# power_switcher.net
KiCad netlist of a schematic drawn in EAGLE
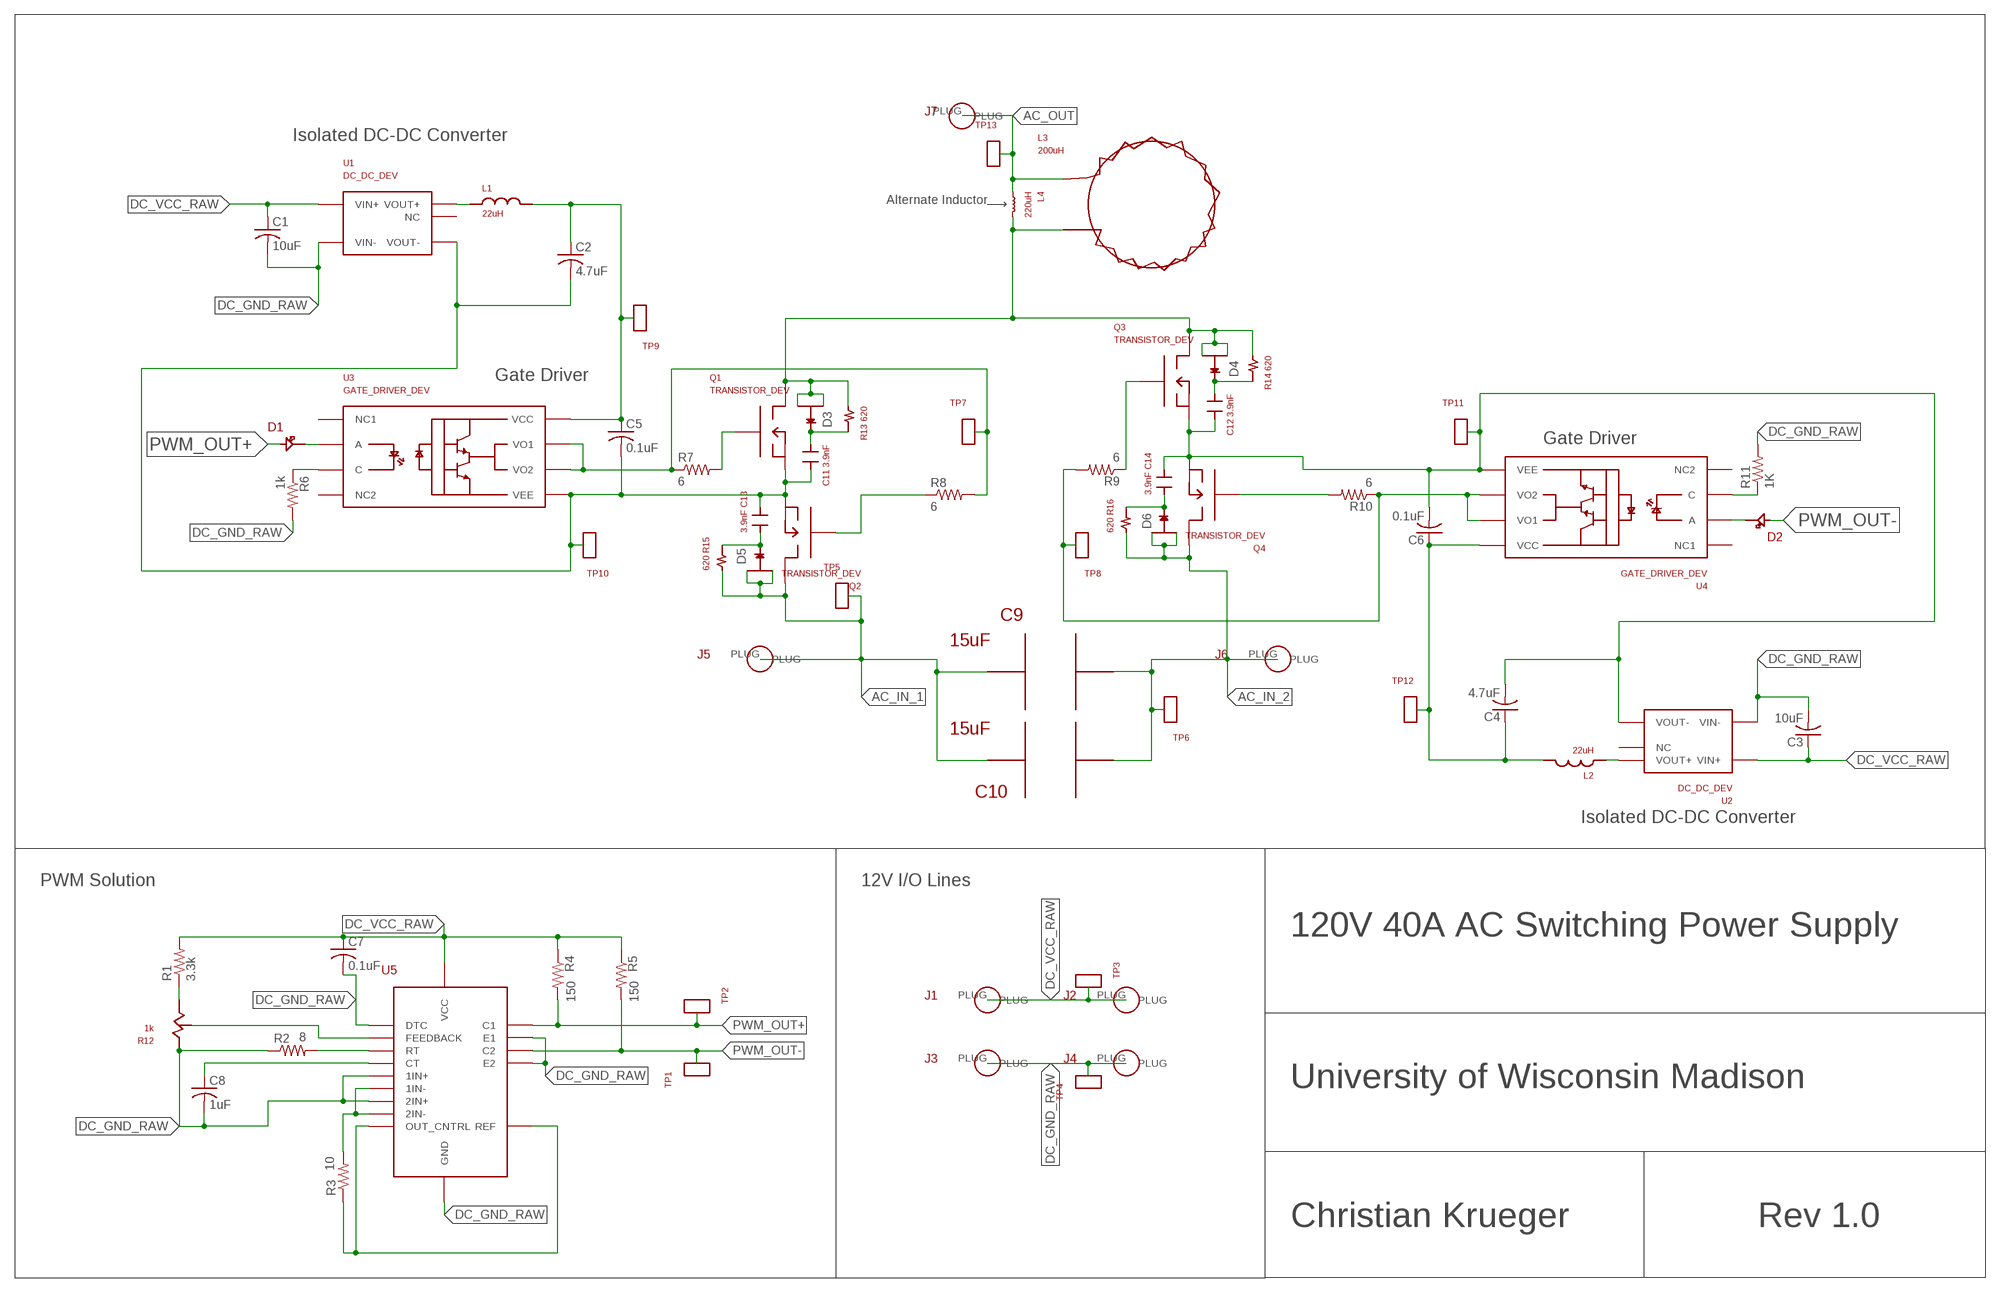
[diagram p0: schematic, sheet 1]

(export (version "E")
  (design (tool "Eeschema 10.0.6"))
  (components
    (comp (ref "C1")
      (value "10uF")
      (footprint "eagle-import:C0805")
      (libsource (lib "eagle-import") (part "C-USC0805"))
    )
    (comp (ref "C2")
      (value "4.7uF")
      (footprint "eagle-import:C0805")
      (libsource (lib "eagle-import") (part "C-USC0805"))
    )
    (comp (ref "C3")
      (value "10uF")
      (footprint "eagle-import:C0805")
      (libsource (lib "eagle-import") (part "C-USC0805"))
    )
    (comp (ref "C4")
      (value "4.7uF")
      (footprint "eagle-import:C0805")
      (libsource (lib "eagle-import") (part "C-USC0805"))
    )
    (comp (ref "C5")
      (value "0.1uF")
      (footprint "eagle-import:C0805")
      (libsource (lib "eagle-import") (part "C-USC0805"))
    )
    (comp (ref "C6")
      (value "0.1uF")
      (footprint "eagle-import:C0805")
      (libsource (lib "eagle-import") (part "C-USC0805"))
    )
    (comp (ref "C7")
      (value "0.1uF")
      (footprint "eagle-import:C0805")
      (libsource (lib "eagle-import") (part "C-USC0805"))
    )
    (comp (ref "C8")
      (value "1uF")
      (footprint "eagle-import:C0805")
      (libsource (lib "eagle-import") (part "C-USC0805"))
    )
    (comp (ref "C9")
      (value "15uF")
      (footprint "eagle-import:BIG_ASS_CAP_PKG")
      (libsource (lib "eagle-import") (part "BIG_AS_CAP_DEV"))
    )
    (comp (ref "C10")
      (value "15uF")
      (footprint "eagle-import:BIG_ASS_CAP_PKG")
      (libsource (lib "eagle-import") (part "BIG_AS_CAP_DEV"))
    )
    (comp (ref "C11")
      (value "3.9nF")
      (footprint "eagle-import:0805_GEN_PKG")
      (libsource (lib "eagle-import") (part "GEN_CAP"))
    )
    (comp (ref "C12")
      (value "3.9nF")
      (footprint "eagle-import:0805_GEN_PKG")
      (libsource (lib "eagle-import") (part "GEN_CAP"))
    )
    (comp (ref "C13")
      (value "3.9nF")
      (footprint "eagle-import:0805_GEN_PKG")
      (libsource (lib "eagle-import") (part "GEN_CAP"))
    )
    (comp (ref "C14")
      (value "3.9nF")
      (footprint "eagle-import:0805_GEN_PKG")
      (libsource (lib "eagle-import") (part "GEN_CAP"))
    )
    (comp (ref "D1")
      (value "LED_DEV")
      (footprint "eagle-import:0805_PKG")
      (libsource (lib "eagle-import") (part "LED_DEV"))
    )
    (comp (ref "D2")
      (value "LED_DEV")
      (footprint "eagle-import:0805_PKG")
      (libsource (lib "eagle-import") (part "LED_DEV"))
    )
    (comp (ref "D3")
      (value "D2PAK_DIODE_DEV")
      (footprint "eagle-import:D2PAK_PKG")
      (libsource (lib "eagle-import") (part "D2PAK_DIODE_DEV"))
    )
    (comp (ref "D4")
      (value "D2PAK_DIODE_DEV")
      (footprint "eagle-import:D2PAK_PKG")
      (libsource (lib "eagle-import") (part "D2PAK_DIODE_DEV"))
    )
    (comp (ref "D5")
      (value "D2PAK_DIODE_DEV")
      (footprint "eagle-import:D2PAK_PKG")
      (libsource (lib "eagle-import") (part "D2PAK_DIODE_DEV"))
    )
    (comp (ref "D6")
      (value "D2PAK_DIODE_DEV")
      (footprint "eagle-import:D2PAK_PKG")
      (libsource (lib "eagle-import") (part "D2PAK_DIODE_DEV"))
    )
    (comp (ref "J1")
      (value "BANNANA_DEV")
      (footprint "eagle-import:BANNANA_PKG")
      (libsource (lib "eagle-import") (part "BANNANA_DEV"))
    )
    (comp (ref "J2")
      (value "BANNANA_DEV")
      (footprint "eagle-import:BANNANA_PKG")
      (libsource (lib "eagle-import") (part "BANNANA_DEV"))
    )
    (comp (ref "J3")
      (value "BANNANA_DEV")
      (footprint "eagle-import:BANNANA_PKG")
      (libsource (lib "eagle-import") (part "BANNANA_DEV"))
    )
    (comp (ref "J4")
      (value "BANNANA_DEV")
      (footprint "eagle-import:BANNANA_PKG")
      (libsource (lib "eagle-import") (part "BANNANA_DEV"))
    )
    (comp (ref "J5")
      (value "BANNANA_DEV")
      (footprint "eagle-import:BANNANA_PKG")
      (libsource (lib "eagle-import") (part "BANNANA_DEV"))
    )
    (comp (ref "J6")
      (value "BANNANA_DEV")
      (footprint "eagle-import:BANNANA_PKG")
      (libsource (lib "eagle-import") (part "BANNANA_DEV"))
    )
    (comp (ref "J7")
      (value "BANNANA_DEV")
      (footprint "eagle-import:BANNANA_PKG")
      (libsource (lib "eagle-import") (part "BANNANA_DEV"))
    )
    (comp (ref "L1")
      (value "22uH")
      (footprint "eagle-import:0805RES_DEV")
      (libsource (lib "eagle-import") (part "0805IND_DEV"))
    )
    (comp (ref "L2")
      (value "22uH")
      (footprint "eagle-import:0805RES_DEV")
      (libsource (lib "eagle-import") (part "0805IND_DEV"))
    )
    (comp (ref "L3")
      (value "200uH")
      (footprint "eagle-import:BIG_ASS_INDUCTOR_PKG")
      (libsource (lib "eagle-import") (part "BIG_ASS_INDUCTOR"))
    )
    (comp (ref "L4")
      (value "220uH")
      (footprint "eagle-import:ALT_IND_PKG")
      (libsource (lib "eagle-import") (part "ALT_IND_DEV"))
    )
    (comp (ref "Q1")
      (value "TRANSISTOR_DEV")
      (footprint "eagle-import:TRANSISTOR_PKG")
      (libsource (lib "eagle-import") (part "TRANSISTOR_DEV"))
    )
    (comp (ref "Q2")
      (value "TRANSISTOR_DEV")
      (footprint "eagle-import:TRANSISTOR_PKG")
      (libsource (lib "eagle-import") (part "TRANSISTOR_DEV"))
    )
    (comp (ref "Q3")
      (value "TRANSISTOR_DEV")
      (footprint "eagle-import:TRANSISTOR_PKG")
      (libsource (lib "eagle-import") (part "TRANSISTOR_DEV"))
    )
    (comp (ref "Q4")
      (value "TRANSISTOR_DEV")
      (footprint "eagle-import:TRANSISTOR_PKG")
      (libsource (lib "eagle-import") (part "TRANSISTOR_DEV"))
    )
    (comp (ref "R1")
      (value "3.3k")
      (footprint "eagle-import:M0805")
      (libsource (lib "eagle-import") (part "R-US_M0805"))
    )
    (comp (ref "R2")
      (value "8")
      (footprint "eagle-import:M0805")
      (libsource (lib "eagle-import") (part "R-US_M0805"))
    )
    (comp (ref "R3")
      (value "10")
      (footprint "eagle-import:M0805")
      (libsource (lib "eagle-import") (part "R-US_M0805"))
    )
    (comp (ref "R4")
      (value "150")
      (footprint "eagle-import:M0805")
      (libsource (lib "eagle-import") (part "R-US_M0805"))
    )
    (comp (ref "R5")
      (value "150")
      (footprint "eagle-import:M0805")
      (libsource (lib "eagle-import") (part "R-US_M0805"))
    )
    (comp (ref "R6")
      (value "1k")
      (footprint "eagle-import:M0805")
      (libsource (lib "eagle-import") (part "R-US_M0805"))
    )
    (comp (ref "R7")
      (value "6")
      (footprint "eagle-import:M0805")
      (libsource (lib "eagle-import") (part "R-US_M0805"))
    )
    (comp (ref "R8")
      (value "6")
      (footprint "eagle-import:M0805")
      (libsource (lib "eagle-import") (part "R-US_M0805"))
    )
    (comp (ref "R9")
      (value "6")
      (footprint "eagle-import:M0805")
      (libsource (lib "eagle-import") (part "R-US_M0805"))
    )
    (comp (ref "R10")
      (value "6")
      (footprint "eagle-import:M0805")
      (libsource (lib "eagle-import") (part "R-US_M0805"))
    )
    (comp (ref "R11")
      (value "1K")
      (footprint "eagle-import:M0805")
      (libsource (lib "eagle-import") (part "R-US_M0805"))
    )
    (comp (ref "R12")
      (value "1k")
      (footprint "eagle-import:POT_SLIDER_PKG")
      (libsource (lib "eagle-import") (part "SLIDE_POT_DEV"))
    )
    (comp (ref "R13")
      (value "620")
      (footprint "eagle-import:2512_PKG")
      (libsource (lib "eagle-import") (part "2512_RES"))
    )
    (comp (ref "R14")
      (value "620")
      (footprint "eagle-import:2512_PKG")
      (libsource (lib "eagle-import") (part "2512_RES"))
    )
    (comp (ref "R15")
      (value "620")
      (footprint "eagle-import:2512_PKG")
      (libsource (lib "eagle-import") (part "2512_RES"))
    )
    (comp (ref "R16")
      (value "620")
      (footprint "eagle-import:2512_PKG")
      (libsource (lib "eagle-import") (part "2512_RES"))
    )
    (comp (ref "TP1")
      (value "TEST_POINT")
      (footprint "eagle-import:0805_GEN_PKG")
      (libsource (lib "eagle-import") (part "TEST_POINT"))
    )
    (comp (ref "TP2")
      (value "TEST_POINT")
      (footprint "eagle-import:0805_GEN_PKG")
      (libsource (lib "eagle-import") (part "TEST_POINT"))
    )
    (comp (ref "TP3")
      (value "TEST_POINT")
      (footprint "eagle-import:0805_GEN_PKG")
      (libsource (lib "eagle-import") (part "TEST_POINT"))
    )
    (comp (ref "TP4")
      (value "TEST_POINT")
      (footprint "eagle-import:0805_GEN_PKG")
      (libsource (lib "eagle-import") (part "TEST_POINT"))
    )
    (comp (ref "TP5")
      (value "TEST_POINT")
      (footprint "eagle-import:0805_GEN_PKG")
      (libsource (lib "eagle-import") (part "TEST_POINT"))
    )
    (comp (ref "TP6")
      (value "TEST_POINT")
      (footprint "eagle-import:0805_GEN_PKG")
      (libsource (lib "eagle-import") (part "TEST_POINT"))
    )
    (comp (ref "TP7")
      (value "TEST_POINT")
      (footprint "eagle-import:0805_GEN_PKG")
      (libsource (lib "eagle-import") (part "TEST_POINT"))
    )
    (comp (ref "TP8")
      (value "TEST_POINT")
      (footprint "eagle-import:0805_GEN_PKG")
      (libsource (lib "eagle-import") (part "TEST_POINT"))
    )
    (comp (ref "TP9")
      (value "TEST_POINT")
      (footprint "eagle-import:0805_GEN_PKG")
      (libsource (lib "eagle-import") (part "TEST_POINT"))
    )
    (comp (ref "TP10")
      (value "TEST_POINT")
      (footprint "eagle-import:0805_GEN_PKG")
      (libsource (lib "eagle-import") (part "TEST_POINT"))
    )
    (comp (ref "TP11")
      (value "TEST_POINT")
      (footprint "eagle-import:0805_GEN_PKG")
      (libsource (lib "eagle-import") (part "TEST_POINT"))
    )
    (comp (ref "TP12")
      (value "TEST_POINT")
      (footprint "eagle-import:0805_GEN_PKG")
      (libsource (lib "eagle-import") (part "TEST_POINT"))
    )
    (comp (ref "TP13")
      (value "TEST_POINT")
      (footprint "eagle-import:0805_GEN_PKG")
      (libsource (lib "eagle-import") (part "TEST_POINT"))
    )
    (comp (ref "U1")
      (value "DC_DC_DEV")
      (footprint "eagle-import:DC_DC_PKG")
      (libsource (lib "eagle-import") (part "DC_DC_DEV"))
    )
    (comp (ref "U2")
      (value "DC_DC_DEV")
      (footprint "eagle-import:DC_DC_PKG")
      (libsource (lib "eagle-import") (part "DC_DC_DEV"))
    )
    (comp (ref "U3")
      (value "GATE_DRIVER_DEV")
      (footprint "eagle-import:GATE_DRIVER_PKG")
      (libsource (lib "eagle-import") (part "GATE_DRIVER_DEV"))
    )
    (comp (ref "U4")
      (value "GATE_DRIVER_DEV")
      (footprint "eagle-import:GATE_DRIVER_PKG")
      (libsource (lib "eagle-import") (part "GATE_DRIVER_DEV"))
    )
    (comp (ref "U5")
      (value "PWM_DRIVER_DEV")
      (footprint "eagle-import:PWM_DRIVER_PKG")
      (libsource (lib "eagle-import") (part "PWM_DRIVER_DEV"))
    )
  )
  (nets
    (net (code "1") (name "AC_IN_1") (class "Default")
      (node (ref "C10") (pin "P$1") (pinfunction "P$1_P$1") (pintype "bidirectional"))
      (node (ref "C9") (pin "P$1") (pinfunction "P$1_P$1") (pintype "bidirectional"))
      (node (ref "D5") (pin "IN1") (pinfunction "IN1_IN1") (pintype "bidirectional"))
      (node (ref "D5") (pin "IN2") (pinfunction "IN2_IN2") (pintype "bidirectional"))
      (node (ref "J5") (pin "PLUG") (pinfunction "PLUG_PLUG") (pintype "bidirectional"))
      (node (ref "Q2") (pin "D") (pinfunction "DRAIN_D") (pintype "bidirectional"))
      (node (ref "R15") (pin "P$1") (pinfunction "P$1_P$1") (pintype "bidirectional"))
      (node (ref "TP5") (pin "P$1") (pinfunction "P$1_P$1") (pintype "bidirectional"))
    )
    (net (code "2") (name "AC_IN_2") (class "Default")
      (node (ref "C10") (pin "P$2") (pinfunction "P$2_P$2") (pintype "bidirectional"))
      (node (ref "C9") (pin "P$2") (pinfunction "P$2_P$2") (pintype "bidirectional"))
      (node (ref "D6") (pin "IN1") (pinfunction "IN1_IN1") (pintype "bidirectional"))
      (node (ref "D6") (pin "IN2") (pinfunction "IN2_IN2") (pintype "bidirectional"))
      (node (ref "J6") (pin "PLUG") (pinfunction "PLUG_PLUG") (pintype "bidirectional"))
      (node (ref "Q4") (pin "D") (pinfunction "DRAIN_D") (pintype "bidirectional"))
      (node (ref "R16") (pin "P$1") (pinfunction "P$1_P$1") (pintype "bidirectional"))
      (node (ref "TP6") (pin "P$1") (pinfunction "P$1_P$1") (pintype "bidirectional"))
    )
    (net (code "3") (name "AC_OUT") (class "Default")
      (node (ref "J7") (pin "PLUG") (pinfunction "PLUG_PLUG") (pintype "bidirectional"))
      (node (ref "L3") (pin "P$1") (pinfunction "P$1_P$1") (pintype "bidirectional"))
      (node (ref "L4") (pin "P$1") (pinfunction "P$1_P$1") (pintype "bidirectional"))
      (node (ref "TP13") (pin "P$1") (pinfunction "P$1_P$1") (pintype "bidirectional"))
    )
    (net (code "4") (name "DC_GND_RAW") (class "Default")
      (node (ref "C1") (pin "2") (pinfunction "2_2") (pintype "passive"))
      (node (ref "C3") (pin "2") (pinfunction "2_2") (pintype "passive"))
      (node (ref "C7") (pin "2") (pinfunction "2_2") (pintype "passive"))
      (node (ref "C8") (pin "2") (pinfunction "2_2") (pintype "passive"))
      (node (ref "J3") (pin "PLUG") (pinfunction "PLUG_PLUG") (pintype "bidirectional"))
      (node (ref "J4") (pin "PLUG") (pinfunction "PLUG_PLUG") (pintype "bidirectional"))
      (node (ref "R11") (pin "2") (pinfunction "2_2") (pintype "passive"))
      (node (ref "R12") (pin "3") (pinfunction "1_3") (pintype "bidirectional"))
      (node (ref "R2") (pin "1") (pinfunction "1_1") (pintype "passive"))
      (node (ref "R6") (pin "2") (pinfunction "2_2") (pintype "passive"))
      (node (ref "TP4") (pin "P$1") (pinfunction "P$1_P$1") (pintype "bidirectional"))
      (node (ref "U1") (pin "-VIN") (pinfunction "VIN-_-VIN") (pintype "bidirectional"))
      (node (ref "U2") (pin "-VIN") (pinfunction "VIN-_-VIN") (pintype "bidirectional"))
      (node (ref "U5") (pin "P$1") (pinfunction "1IN+_P$1") (pintype "bidirectional"))
      (node (ref "U5") (pin "P$10") (pinfunction "E2_P$10") (pintype "bidirectional"))
      (node (ref "U5") (pin "P$16") (pinfunction "2IN+_P$16") (pintype "bidirectional"))
      (node (ref "U5") (pin "P$4") (pinfunction "DTC_P$4") (pintype "bidirectional"))
      (node (ref "U5") (pin "P$7") (pinfunction "GND_P$7") (pintype "bidirectional"))
      (node (ref "U5") (pin "P$9") (pinfunction "E1_P$9") (pintype "bidirectional"))
    )
    (net (code "5") (name "DC_VCC_RAW") (class "Default")
      (node (ref "C1") (pin "1") (pinfunction "1_1") (pintype "passive"))
      (node (ref "C3") (pin "1") (pinfunction "1_1") (pintype "passive"))
      (node (ref "C7") (pin "1") (pinfunction "1_1") (pintype "passive"))
      (node (ref "J1") (pin "PLUG") (pinfunction "PLUG_PLUG") (pintype "bidirectional"))
      (node (ref "J2") (pin "PLUG") (pinfunction "PLUG_PLUG") (pintype "bidirectional"))
      (node (ref "R1") (pin "2") (pinfunction "2_2") (pintype "passive"))
      (node (ref "R4") (pin "1") (pinfunction "1_1") (pintype "passive"))
      (node (ref "R5") (pin "1") (pinfunction "1_1") (pintype "passive"))
      (node (ref "TP3") (pin "P$1") (pinfunction "P$1_P$1") (pintype "bidirectional"))
      (node (ref "U1") (pin "+VIN") (pinfunction "VIN+_+VIN") (pintype "bidirectional"))
      (node (ref "U2") (pin "+VIN") (pinfunction "VIN+_+VIN") (pintype "bidirectional"))
      (node (ref "U5") (pin "P$12") (pinfunction "VCC_P$12") (pintype "bidirectional"))
    )
    (net (code "6") (name "Net-(C11-PadP$1)") (class "Default")
      (node (ref "C11") (pin "P$1") (pinfunction "P$1_P$1") (pintype "bidirectional"))
      (node (ref "D3") (pin "OUT") (pinfunction "OUT_OUT") (pintype "bidirectional"))
      (node (ref "R13") (pin "P$2") (pinfunction "P$2_P$2") (pintype "bidirectional"))
    )
    (net (code "7") (name "Net-(C12-PadP$1)") (class "Default")
      (node (ref "C12") (pin "P$1") (pinfunction "P$1_P$1") (pintype "bidirectional"))
      (node (ref "D4") (pin "OUT") (pinfunction "OUT_OUT") (pintype "bidirectional"))
      (node (ref "R14") (pin "P$2") (pinfunction "P$2_P$2") (pintype "bidirectional"))
    )
    (net (code "8") (name "Net-(C13-PadP$1)") (class "Default")
      (node (ref "C13") (pin "P$1") (pinfunction "P$1_P$1") (pintype "bidirectional"))
      (node (ref "D5") (pin "OUT") (pinfunction "OUT_OUT") (pintype "bidirectional"))
      (node (ref "R15") (pin "P$2") (pinfunction "P$2_P$2") (pintype "bidirectional"))
    )
    (net (code "9") (name "Net-(C14-PadP$1)") (class "Default")
      (node (ref "C14") (pin "P$1") (pinfunction "P$1_P$1") (pintype "bidirectional"))
      (node (ref "D6") (pin "OUT") (pinfunction "OUT_OUT") (pintype "bidirectional"))
      (node (ref "R16") (pin "P$2") (pinfunction "P$2_P$2") (pintype "bidirectional"))
    )
    (net (code "10") (name "Net-(D1-PadP$2)") (class "Default")
      (node (ref "D1") (pin "P$2") (pinfunction "P$2_P$2") (pintype "bidirectional"))
      (node (ref "U3") (pin "A") (pinfunction "A_A") (pintype "bidirectional"))
    )
    (net (code "11") (name "Net-(D2-PadP$2)") (class "Default")
      (node (ref "D2") (pin "P$2") (pinfunction "P$2_P$2") (pintype "bidirectional"))
      (node (ref "U4") (pin "A") (pinfunction "A_A") (pintype "bidirectional"))
    )
    (net (code "12") (name "Net-(L1-P$1)") (class "Default")
      (node (ref "L1") (pin "L") (pinfunction "P$1_L") (pintype "bidirectional"))
      (node (ref "U1") (pin "+VOUT") (pinfunction "VOUT+_+VOUT") (pintype "bidirectional"))
    )
    (net (code "13") (name "Net-(L1-P$2)") (class "Default")
      (node (ref "C2") (pin "1") (pinfunction "1_1") (pintype "passive"))
      (node (ref "C5") (pin "1") (pinfunction "1_1") (pintype "passive"))
      (node (ref "L1") (pin "R") (pinfunction "P$2_R") (pintype "bidirectional"))
      (node (ref "TP9") (pin "P$1") (pinfunction "P$1_P$1") (pintype "bidirectional"))
      (node (ref "U3") (pin "VCC") (pinfunction "VCC_VCC") (pintype "bidirectional"))
    )
    (net (code "14") (name "Net-(L2-P$1)") (class "Default")
      (node (ref "L2") (pin "L") (pinfunction "P$1_L") (pintype "bidirectional"))
      (node (ref "U2") (pin "+VOUT") (pinfunction "VOUT+_+VOUT") (pintype "bidirectional"))
    )
    (net (code "15") (name "Net-(L2-P$2)") (class "Default")
      (node (ref "C4") (pin "1") (pinfunction "1_1") (pintype "passive"))
      (node (ref "C6") (pin "1") (pinfunction "1_1") (pintype "passive"))
      (node (ref "L2") (pin "R") (pinfunction "P$2_R") (pintype "bidirectional"))
      (node (ref "TP12") (pin "P$1") (pinfunction "P$1_P$1") (pintype "bidirectional"))
      (node (ref "U4") (pin "VCC") (pinfunction "VCC_VCC") (pintype "bidirectional"))
    )
    (net (code "16") (name "Net-(Q1-DRAIN)") (class "Default")
      (node (ref "D3") (pin "IN1") (pinfunction "IN1_IN1") (pintype "bidirectional"))
      (node (ref "D3") (pin "IN2") (pinfunction "IN2_IN2") (pintype "bidirectional"))
      (node (ref "D4") (pin "IN1") (pinfunction "IN1_IN1") (pintype "bidirectional"))
      (node (ref "D4") (pin "IN2") (pinfunction "IN2_IN2") (pintype "bidirectional"))
      (node (ref "L3") (pin "P$2") (pinfunction "P$2_P$2") (pintype "bidirectional"))
      (node (ref "L4") (pin "P$2") (pinfunction "P$2_P$2") (pintype "bidirectional"))
      (node (ref "Q1") (pin "D") (pinfunction "DRAIN_D") (pintype "bidirectional"))
      (node (ref "Q3") (pin "D") (pinfunction "DRAIN_D") (pintype "bidirectional"))
      (node (ref "R13") (pin "P$1") (pinfunction "P$1_P$1") (pintype "bidirectional"))
      (node (ref "R14") (pin "P$1") (pinfunction "P$1_P$1") (pintype "bidirectional"))
    )
    (net (code "17") (name "Net-(Q1-GATE)") (class "Default")
      (node (ref "Q1") (pin "G") (pinfunction "GATE_G") (pintype "bidirectional"))
      (node (ref "R7") (pin "2") (pinfunction "2_2") (pintype "passive"))
    )
    (net (code "18") (name "Net-(Q1-SOURCE)") (class "Default")
      (node (ref "C11") (pin "P$2") (pinfunction "P$2_P$2") (pintype "bidirectional"))
      (node (ref "C13") (pin "P$2") (pinfunction "P$2_P$2") (pintype "bidirectional"))
      (node (ref "C2") (pin "2") (pinfunction "2_2") (pintype "passive"))
      (node (ref "C5") (pin "2") (pinfunction "2_2") (pintype "passive"))
      (node (ref "Q1") (pin "S") (pinfunction "SOURCE_S") (pintype "bidirectional"))
      (node (ref "Q2") (pin "S") (pinfunction "SOURCE_S") (pintype "bidirectional"))
      (node (ref "TP10") (pin "P$1") (pinfunction "P$1_P$1") (pintype "bidirectional"))
      (node (ref "U1") (pin "-VOUT") (pinfunction "VOUT-_-VOUT") (pintype "bidirectional"))
      (node (ref "U3") (pin "VEE") (pinfunction "VEE_VEE") (pintype "bidirectional"))
    )
    (net (code "19") (name "Net-(Q2-GATE)") (class "Default")
      (node (ref "Q2") (pin "G") (pinfunction "GATE_G") (pintype "bidirectional"))
      (node (ref "R8") (pin "1") (pinfunction "1_1") (pintype "passive"))
    )
    (net (code "20") (name "Net-(Q3-GATE)") (class "Default")
      (node (ref "Q3") (pin "G") (pinfunction "GATE_G") (pintype "bidirectional"))
      (node (ref "R9") (pin "1") (pinfunction "1_1") (pintype "passive"))
    )
    (net (code "21") (name "Net-(Q3-SOURCE)") (class "Default")
      (node (ref "C12") (pin "P$2") (pinfunction "P$2_P$2") (pintype "bidirectional"))
      (node (ref "C14") (pin "P$2") (pinfunction "P$2_P$2") (pintype "bidirectional"))
      (node (ref "C4") (pin "2") (pinfunction "2_2") (pintype "passive"))
      (node (ref "C6") (pin "2") (pinfunction "2_2") (pintype "passive"))
      (node (ref "Q3") (pin "S") (pinfunction "SOURCE_S") (pintype "bidirectional"))
      (node (ref "Q4") (pin "S") (pinfunction "SOURCE_S") (pintype "bidirectional"))
      (node (ref "TP11") (pin "P$1") (pinfunction "P$1_P$1") (pintype "bidirectional"))
      (node (ref "U2") (pin "-VOUT") (pinfunction "VOUT-_-VOUT") (pintype "bidirectional"))
      (node (ref "U4") (pin "VEE") (pinfunction "VEE_VEE") (pintype "bidirectional"))
    )
    (net (code "22") (name "Net-(Q4-GATE)") (class "Default")
      (node (ref "Q4") (pin "G") (pinfunction "GATE_G") (pintype "bidirectional"))
      (node (ref "R10") (pin "2") (pinfunction "2_2") (pintype "passive"))
    )
    (net (code "23") (name "Net-(R6-Pad1)") (class "Default")
      (node (ref "R6") (pin "1") (pinfunction "1_1") (pintype "passive"))
      (node (ref "U3") (pin "C") (pinfunction "C_C") (pintype "bidirectional"))
    )
    (net (code "24") (name "Net-(R7-Pad1)") (class "Default")
      (node (ref "R7") (pin "1") (pinfunction "1_1") (pintype "passive"))
      (node (ref "R8") (pin "2") (pinfunction "2_2") (pintype "passive"))
      (node (ref "TP7") (pin "P$1") (pinfunction "P$1_P$1") (pintype "bidirectional"))
      (node (ref "U3") (pin "VO1") (pinfunction "VO1_VO1") (pintype "bidirectional"))
      (node (ref "U3") (pin "VO2") (pinfunction "VO2_VO2") (pintype "bidirectional"))
    )
    (net (code "25") (name "Net-(R10-Pad1)") (class "Default")
      (node (ref "R10") (pin "1") (pinfunction "1_1") (pintype "passive"))
      (node (ref "R9") (pin "2") (pinfunction "2_2") (pintype "passive"))
      (node (ref "TP8") (pin "P$1") (pinfunction "P$1_P$1") (pintype "bidirectional"))
      (node (ref "U4") (pin "VO1") (pinfunction "VO1_VO1") (pintype "bidirectional"))
      (node (ref "U4") (pin "VO2") (pinfunction "VO2_VO2") (pintype "bidirectional"))
    )
    (net (code "26") (name "Net-(R11-Pad1)") (class "Default")
      (node (ref "R11") (pin "1") (pinfunction "1_1") (pintype "passive"))
      (node (ref "U4") (pin "C") (pinfunction "C_C") (pintype "bidirectional"))
    )
    (net (code "27") (name "Net-(R12-2)") (class "Default")
      (node (ref "R1") (pin "1") (pinfunction "1_1") (pintype "passive"))
      (node (ref "R12") (pin "1") (pinfunction "2_1") (pintype "bidirectional"))
    )
    (net (code "28") (name "Net-(R12-VAR)") (class "Default")
      (node (ref "R12") (pin "2") (pinfunction "VAR_2") (pintype "bidirectional"))
      (node (ref "U5") (pin "P$3") (pinfunction "FEEDBACK_P$3") (pintype "bidirectional"))
    )
    (net (code "29") (name "Net-(U5-1IN-)") (class "Default")
      (node (ref "R3") (pin "2") (pinfunction "2_2") (pintype "passive"))
      (node (ref "U5") (pin "P$15") (pinfunction "2IN-_P$15") (pintype "bidirectional"))
      (node (ref "U5") (pin "P$2") (pinfunction "1IN-_P$2") (pintype "bidirectional"))
    )
    (net (code "30") (name "Net-(U5-CT)") (class "Default")
      (node (ref "C8") (pin "1") (pinfunction "1_1") (pintype "passive"))
      (node (ref "U5") (pin "P$5") (pinfunction "CT_P$5") (pintype "bidirectional"))
    )
    (net (code "31") (name "Net-(U5-OUT_CNTRL)") (class "Default")
      (node (ref "R3") (pin "1") (pinfunction "1_1") (pintype "passive"))
      (node (ref "U5") (pin "P$13") (pinfunction "OUT_CNTRL_P$13") (pintype "bidirectional"))
      (node (ref "U5") (pin "P$14") (pinfunction "REF_P$14") (pintype "bidirectional"))
    )
    (net (code "32") (name "Net-(U5-RT)") (class "Default")
      (node (ref "R2") (pin "2") (pinfunction "2_2") (pintype "passive"))
      (node (ref "U5") (pin "P$6") (pinfunction "RT_P$6") (pintype "bidirectional"))
    )
    (net (code "33") (name "PWM_OUT+") (class "Default")
      (node (ref "D1") (pin "P$1") (pinfunction "P$1_P$1") (pintype "bidirectional"))
      (node (ref "R4") (pin "2") (pinfunction "2_2") (pintype "passive"))
      (node (ref "TP2") (pin "P$1") (pinfunction "P$1_P$1") (pintype "bidirectional"))
      (node (ref "U5") (pin "P$8") (pinfunction "C1_P$8") (pintype "bidirectional"))
    )
    (net (code "34") (name "PWM_OUT-") (class "Default")
      (node (ref "D2") (pin "P$1") (pinfunction "P$1_P$1") (pintype "bidirectional"))
      (node (ref "R5") (pin "2") (pinfunction "2_2") (pintype "passive"))
      (node (ref "TP1") (pin "P$1") (pinfunction "P$1_P$1") (pintype "bidirectional"))
      (node (ref "U5") (pin "P$11") (pinfunction "C2_P$11") (pintype "bidirectional"))
    )
    (net (code "35") (name "unconnected-(U1-PadNC)") (class "Default")
      (node (ref "U1") (pin "NC") (pinfunction "NC_NC") (pintype "bidirectional"))
    )
    (net (code "36") (name "unconnected-(U2-PadNC)") (class "Default")
      (node (ref "U2") (pin "NC") (pinfunction "NC_NC") (pintype "bidirectional"))
    )
    (net (code "37") (name "unconnected-(U3-PadNC1)") (class "Default")
      (node (ref "U3") (pin "NC1") (pinfunction "NC1_NC1") (pintype "bidirectional"))
    )
    (net (code "38") (name "unconnected-(U3-PadNC2)") (class "Default")
      (node (ref "U3") (pin "NC2") (pinfunction "NC2_NC2") (pintype "bidirectional"))
    )
    (net (code "39") (name "unconnected-(U4-PadNC1)") (class "Default")
      (node (ref "U4") (pin "NC1") (pinfunction "NC1_NC1") (pintype "bidirectional"))
    )
    (net (code "40") (name "unconnected-(U4-PadNC2)") (class "Default")
      (node (ref "U4") (pin "NC2") (pinfunction "NC2_NC2") (pintype "bidirectional"))
    )
  )
)
